# mcu.net
KiCad netlist of a schematic drawn in Altium Designer
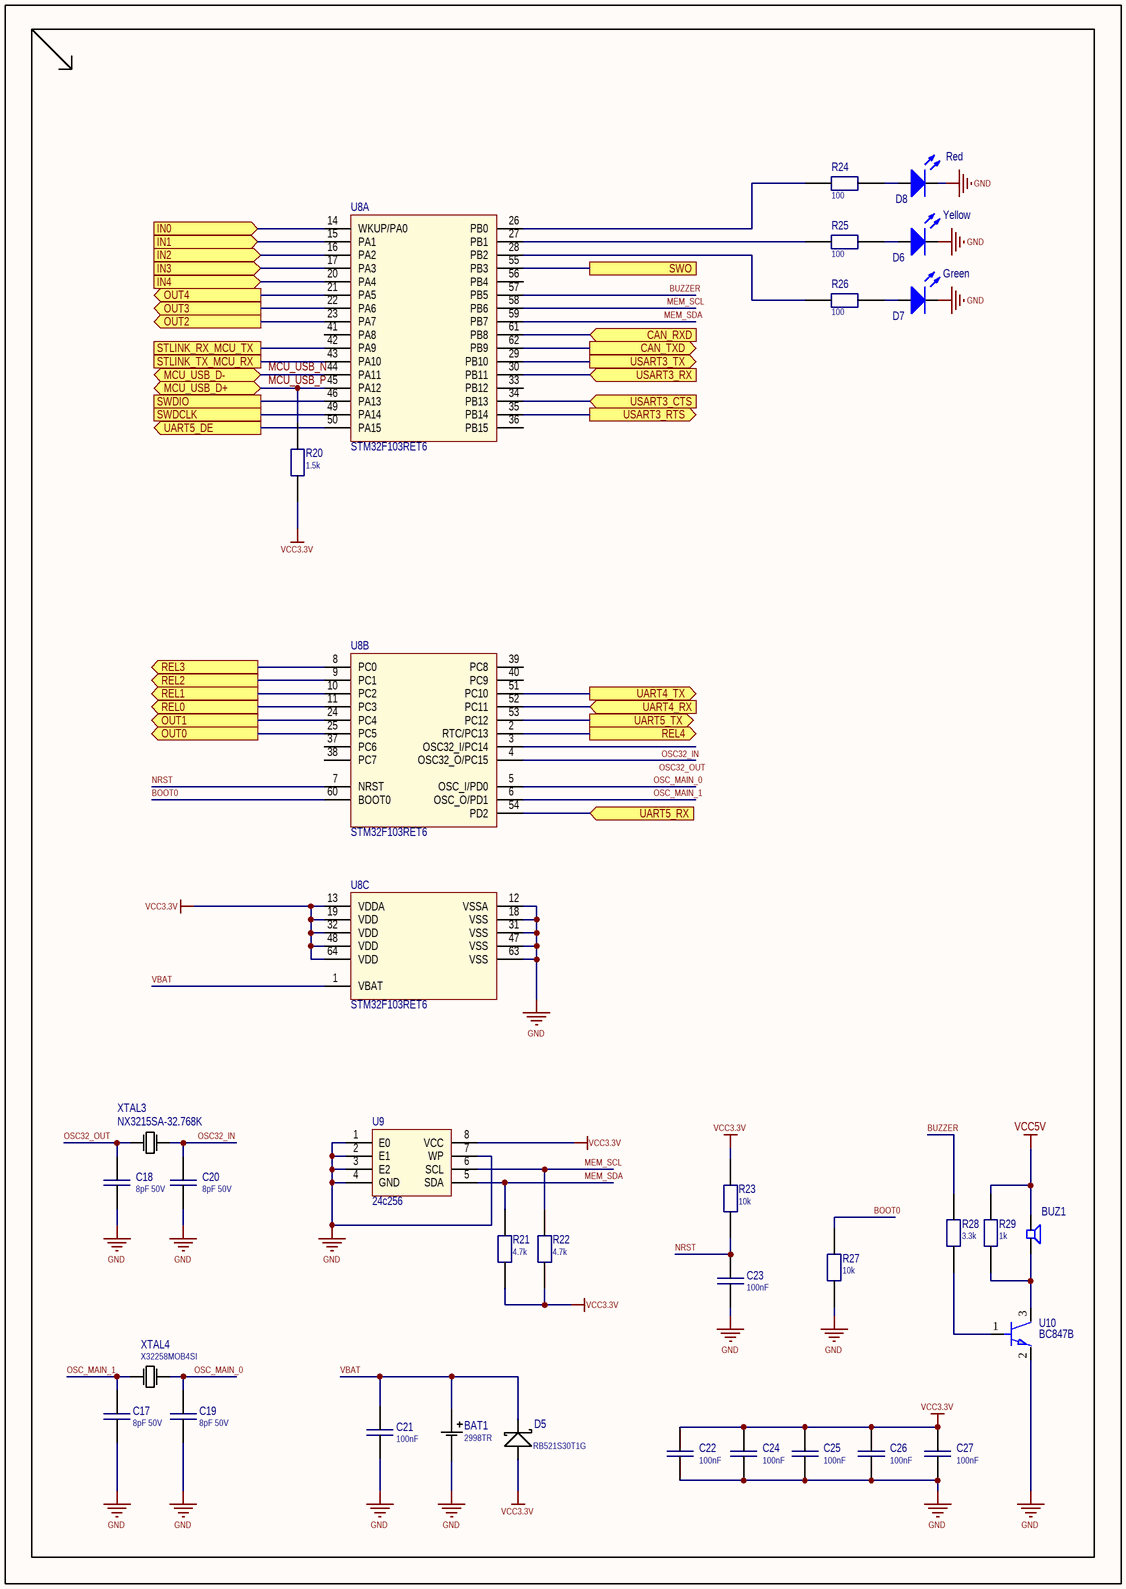
[diagram p0: mcu.schdoc]

(export (version "E")
  (design (tool "Eeschema 10.0.6"))
  (components
    (comp (ref "BAT1")
      (value "2998TR")
      (footprint "BAT_2998TR")
      (description "Battery")
      (libsource (lib "battery_socets") (part "2998TR"))
    )
    (comp (ref "BUZ1")
      (value "L-KLS3-SMT-09X1.8")
      (footprint "SPKR_PKMCS0909E4000-R1")
      (description "Piezoelectric Sounders")
      (fields (field (name "ALTERNATIVE PART") "PKMCS0909E4000-R1"))
      (libsource (lib "other") (part "BUZZER"))
    )
    (comp (ref "C17")
      (value "8pF 50V")
      (footprint "C_0603")
      (description "Capacitor")
      (fields (field (name "PART NUMBER") "CC0603DRNPO9BN8R0"))
      (libsource (lib "capacitors") (part "C0603"))
    )
    (comp (ref "C18")
      (value "8pF 50V")
      (footprint "C_0603")
      (description "Capacitor")
      (fields (field (name "PART NUMBER") "CC0603DRNPO9BN8R0"))
      (libsource (lib "capacitors") (part "C0603"))
    )
    (comp (ref "C19")
      (value "8pF 50V")
      (footprint "C_0603")
      (description "Capacitor")
      (fields (field (name "PART NUMBER") "CC0603DRNPO9BN8R0"))
      (libsource (lib "capacitors") (part "C0603"))
    )
    (comp (ref "C20")
      (value "8pF 50V")
      (footprint "C_0603")
      (description "Capacitor")
      (fields (field (name "PART NUMBER") "CC0603DRNPO9BN8R0"))
      (libsource (lib "capacitors") (part "C0603"))
    )
    (comp (ref "C21")
      (value "100nF")
      (footprint "C_0603")
      (description "Capacitor")
      (fields (field (name "PART NUMBER") "CC0603JPX7R9BB104"))
      (libsource (lib "capacitors") (part "C0603"))
    )
    (comp (ref "C22")
      (value "100nF")
      (footprint "C_0603")
      (description "Capacitor")
      (fields (field (name "PART NUMBER") "CC0603JPX7R9BB104"))
      (libsource (lib "capacitors") (part "C0603"))
    )
    (comp (ref "C23")
      (value "100nF")
      (footprint "C_0603")
      (description "Capacitor")
      (fields (field (name "PART NUMBER") "CC0603JPX7R9BB104"))
      (libsource (lib "capacitors") (part "C0603"))
    )
    (comp (ref "C24")
      (value "100nF")
      (footprint "C_0603")
      (description "Capacitor")
      (fields (field (name "PART NUMBER") "CC0603JPX7R9BB104"))
      (libsource (lib "capacitors") (part "C0603"))
    )
    (comp (ref "C25")
      (value "100nF")
      (footprint "C_0603")
      (description "Capacitor")
      (fields (field (name "PART NUMBER") "CC0603JPX7R9BB104"))
      (libsource (lib "capacitors") (part "C0603"))
    )
    (comp (ref "C26")
      (value "100nF")
      (footprint "C_0603")
      (description "Capacitor")
      (fields (field (name "PART NUMBER") "CC0603JPX7R9BB104"))
      (libsource (lib "capacitors") (part "C0603"))
    )
    (comp (ref "C27")
      (value "100nF")
      (footprint "C_0603")
      (description "Capacitor")
      (fields (field (name "PART NUMBER") "CC0603JPX7R9BB104"))
      (libsource (lib "capacitors") (part "C0603"))
    )
    (comp (ref "D5")
      (value "RB521S30T1G")
      (footprint "SOD-523")
      (description "Diode")
      (libsource (lib "diode") (part "D_SOD523"))
    )
    (comp (ref "D6")
      (value "Yellow")
      (footprint "LED_1206")
      (description "Typical INFRARED GaAs LED")
      (fields (field (name "PART NUMBER") "KPT-3216SYC"))
      (libsource (lib "AX_Altium_v2.3") (part "LED_SMT_1206"))
    )
    (comp (ref "D7")
      (value "Green")
      (footprint "LED_1206")
      (description "Typical INFRARED GaAs LED")
      (fields (field (name "PART NUMBER") "KP-3216SGD"))
      (libsource (lib "AX_Altium_v2.3") (part "LED_SMT_1206"))
    )
    (comp (ref "D8")
      (value "Red")
      (footprint "LED_1206")
      (description "Typical INFRARED GaAs LED")
      (fields (field (name "PART NUMBER") "KP-3216SRD"))
      (libsource (lib "AX_Altium_v2.3") (part "LED_SMT_1206"))
    )
    (comp (ref "R20")
      (value "1.5k")
      (footprint "R_0603")
      (description "Resistor")
      (fields (field (name "PART NUMBER") "RC0603FR-071K5L"))
      (libsource (lib "resistors") (part "RES_SMD"))
    )
    (comp (ref "R21")
      (value "4.7k")
      (footprint "R_0603")
      (description "Resistor")
      (fields (field (name "PART NUMBER") "RC0603FR-074K7L"))
      (libsource (lib "resistors") (part "RES_SMD"))
    )
    (comp (ref "R22")
      (value "4.7k")
      (footprint "R_0603")
      (description "Resistor")
      (fields (field (name "PART NUMBER") "RC0603FR-074K7L"))
      (libsource (lib "resistors") (part "RES_SMD"))
    )
    (comp (ref "R23")
      (value "10k")
      (footprint "R_0603")
      (description "Resistor")
      (fields (field (name "PART NUMBER") "RC0603FR-0710KL"))
      (libsource (lib "resistors") (part "RES_SMD"))
    )
    (comp (ref "R24")
      (value "100")
      (footprint "R_0603")
      (description "Resistor")
      (fields (field (name "PART NUMBER") "RC0603FR-07100RL"))
      (libsource (lib "resistors") (part "RES_SMD"))
    )
    (comp (ref "R25")
      (value "100")
      (footprint "R_0603")
      (description "Resistor")
      (fields (field (name "PART NUMBER") "RC0603FR-07100RL"))
      (libsource (lib "resistors") (part "RES_SMD"))
    )
    (comp (ref "R26")
      (value "100")
      (footprint "R_0603")
      (description "Resistor")
      (fields (field (name "PART NUMBER") "RC0603FR-07100RL"))
      (libsource (lib "resistors") (part "RES_SMD"))
    )
    (comp (ref "R27")
      (value "10k")
      (footprint "R_0603")
      (description "Resistor")
      (fields (field (name "PART NUMBER") "RC0603FR-0710KL"))
      (libsource (lib "resistors") (part "RES_SMD"))
    )
    (comp (ref "R28")
      (value "3.3k")
      (footprint "R_0603")
      (description "Resistor")
      (fields (field (name "PART NUMBER") "RC0603FR-073K3L"))
      (libsource (lib "resistors") (part "RES_SMD"))
    )
    (comp (ref "R29")
      (value "1k")
      (footprint "R_0603")
      (description "Resistor")
      (fields (field (name "PART NUMBER") "RC0603FR-071KL"))
      (libsource (lib "resistors") (part "RES_SMD"))
    )
    (comp (ref "U8")
      (value "STM32F103RET6")
      (footprint "LQFP64")
      (libsource (lib "mcu") (part "STM32F103Rxx"))
    )
    (comp (ref "U9")
      (value "24c256")
      (footprint "SO-8_M")
      (description "256-Kbit I2C-compatible Serial EEPROM")
      (fields (field (name "PART NUMBER") "AT24C256C"))
      (libsource (lib "discret_ic") (part "24c256"))
    )
    (comp (ref "U10")
      (value "BC847B")
      (footprint "SOT23")
      (description "45V 200mW 200@2mA,5V 100mA NPN SOT-23-3 Bipolar (BJT)")
      (libsource (lib "AX_Altium_v2.3") (part "BC847B"))
    )
    (comp (ref "XTAL3")
      (value "NX3215SA-32.768K")
      (footprint "XTAL_NX3215SA-32.768K-STD-MUA-8")
      (description "Crystal Oscillator")
      (fields (field (name "PART NUMBER") "NX3215SA-32.768K-10PPM-45KOHM-6PF"))
      (libsource (lib "crystals_oscillators") (part "NX3215SA-32.768K"))
    )
    (comp (ref "XTAL4")
      (value "X32258MOB4SI")
      (footprint "NX3225GA")
      (description "Crystal Oscillator")
      (libsource (lib "bmplc") (part "NX3225GA"))
    )
  )
  (nets
    (net (code "1") (name "/BOOT0") (class "Default")
      (node (ref "R27") (pin "2") (pinfunction "2_2") (pintype "passive"))
      (node (ref "U8") (pin "60") (pinfunction "BOOT0_60") (pintype "passive"))
    )
    (net (code "2") (name "/BUZZER") (class "Default")
      (node (ref "R28") (pin "1") (pinfunction "1_1") (pintype "passive"))
      (node (ref "U8") (pin "57") (pinfunction "PB5_57") (pintype "passive"))
    )
    (net (code "3") (name "/CAN_RXD") (class "Default")
      (node (ref "U8") (pin "61") (pinfunction "PB8_61") (pintype "passive"))
    )
    (net (code "4") (name "/CAN_TXD") (class "Default")
      (node (ref "U8") (pin "62") (pinfunction "PB9_62") (pintype "passive"))
    )
    (net (code "5") (name "/IN0") (class "Default")
      (node (ref "U8") (pin "14") (pinfunction "WKUP/PA0_14") (pintype "passive"))
    )
    (net (code "6") (name "/IN1") (class "Default")
      (node (ref "U8") (pin "15") (pinfunction "PA1_15") (pintype "passive"))
    )
    (net (code "7") (name "/IN2") (class "Default")
      (node (ref "U8") (pin "16") (pinfunction "PA2_16") (pintype "passive"))
    )
    (net (code "8") (name "/IN3") (class "Default")
      (node (ref "U8") (pin "17") (pinfunction "PA3_17") (pintype "passive"))
    )
    (net (code "9") (name "/IN4") (class "Default")
      (node (ref "U8") (pin "20") (pinfunction "PA4_20") (pintype "passive"))
    )
    (net (code "10") (name "/MCU_USB_N") (class "Default")
      (node (ref "U8") (pin "44") (pinfunction "PA11_44") (pintype "passive"))
    )
    (net (code "11") (name "/MCU_USB_P") (class "Default")
      (node (ref "R20") (pin "1") (pinfunction "1_1") (pintype "passive"))
      (node (ref "U8") (pin "45") (pinfunction "PA12_45") (pintype "passive"))
    )
    (net (code "12") (name "/MEM_SCL") (class "Default")
      (node (ref "R22") (pin "1") (pinfunction "1_1") (pintype "passive"))
      (node (ref "U8") (pin "58") (pinfunction "PB6_58") (pintype "passive"))
      (node (ref "U9") (pin "6") (pinfunction "SCL_6") (pintype "passive"))
    )
    (net (code "13") (name "/MEM_SDA") (class "Default")
      (node (ref "R21") (pin "1") (pinfunction "1_1") (pintype "passive"))
      (node (ref "U8") (pin "59") (pinfunction "PB7_59") (pintype "passive"))
      (node (ref "U9") (pin "5") (pinfunction "SDA_5") (pintype "passive"))
    )
    (net (code "14") (name "/NRST") (class "Default")
      (node (ref "C23") (pin "2") (pinfunction "2_2") (pintype "passive"))
      (node (ref "R23") (pin "1") (pinfunction "1_1") (pintype "passive"))
      (node (ref "U8") (pin "7") (pinfunction "NRST_7") (pintype "passive"))
    )
    (net (code "15") (name "/OSC32_IN") (class "Default")
      (node (ref "C20") (pin "2") (pinfunction "2_2") (pintype "passive"))
      (node (ref "U8") (pin "3") (pinfunction "OSC32_I/PC14_3") (pintype "passive"))
      (node (ref "XTAL3") (pin "2") (pinfunction "OSC2_2") (pintype "passive"))
    )
    (net (code "16") (name "/OSC32_OUT") (class "Default")
      (node (ref "C18") (pin "2") (pinfunction "2_2") (pintype "passive"))
      (node (ref "U8") (pin "4") (pinfunction "OSC32_O/PC15_4") (pintype "passive"))
      (node (ref "XTAL3") (pin "1") (pinfunction "OSC1_1") (pintype "passive"))
    )
    (net (code "17") (name "/OSC_MAIN_0") (class "Default")
      (node (ref "C19") (pin "2") (pinfunction "2_2") (pintype "passive"))
      (node (ref "U8") (pin "5") (pinfunction "OSC_I/PD0_5") (pintype "passive"))
      (node (ref "XTAL4") (pin "3") (pinfunction "OSC2_3") (pintype "passive"))
    )
    (net (code "18") (name "/OSC_MAIN_1") (class "Default")
      (node (ref "C17") (pin "2") (pinfunction "2_2") (pintype "passive"))
      (node (ref "U8") (pin "6") (pinfunction "OSC_O/PD1_6") (pintype "passive"))
      (node (ref "XTAL4") (pin "1") (pinfunction "OSC1_1") (pintype "passive"))
    )
    (net (code "19") (name "/OUT0") (class "Default")
      (node (ref "U8") (pin "25") (pinfunction "PC5_25") (pintype "passive"))
    )
    (net (code "20") (name "/OUT1") (class "Default")
      (node (ref "U8") (pin "24") (pinfunction "PC4_24") (pintype "passive"))
    )
    (net (code "21") (name "/OUT2") (class "Default")
      (node (ref "U8") (pin "23") (pinfunction "PA7_23") (pintype "passive"))
    )
    (net (code "22") (name "/OUT3") (class "Default")
      (node (ref "U8") (pin "22") (pinfunction "PA6_22") (pintype "passive"))
    )
    (net (code "23") (name "/OUT4") (class "Default")
      (node (ref "U8") (pin "21") (pinfunction "PA5_21") (pintype "passive"))
    )
    (net (code "24") (name "/REL0") (class "Default")
      (node (ref "U8") (pin "11") (pinfunction "PC3_11") (pintype "passive"))
    )
    (net (code "25") (name "/REL1") (class "Default")
      (node (ref "U8") (pin "10") (pinfunction "PC2_10") (pintype "passive"))
    )
    (net (code "26") (name "/REL2") (class "Default")
      (node (ref "U8") (pin "9") (pinfunction "PC1_9") (pintype "passive"))
    )
    (net (code "27") (name "/REL3") (class "Default")
      (node (ref "U8") (pin "8") (pinfunction "PC0_8") (pintype "passive"))
    )
    (net (code "28") (name "/REL4") (class "Default")
      (node (ref "U8") (pin "2") (pinfunction "RTC/PC13_2") (pintype "passive"))
    )
    (net (code "29") (name "/STLINK_RX_MCU_TX") (class "Default")
      (node (ref "U8") (pin "42") (pinfunction "PA9_42") (pintype "passive"))
    )
    (net (code "30") (name "/STLINK_TX_MCU_RX") (class "Default")
      (node (ref "U8") (pin "43") (pinfunction "PA10_43") (pintype "passive"))
    )
    (net (code "31") (name "/SWDCLK") (class "Default")
      (node (ref "U8") (pin "49") (pinfunction "PA14_49") (pintype "passive"))
    )
    (net (code "32") (name "/SWDIO") (class "Default")
      (node (ref "U8") (pin "46") (pinfunction "PA13_46") (pintype "passive"))
    )
    (net (code "33") (name "/SWO") (class "Default")
      (node (ref "U8") (pin "55") (pinfunction "PB3_55") (pintype "passive"))
    )
    (net (code "34") (name "/UART4_RX") (class "Default")
      (node (ref "U8") (pin "52") (pinfunction "PC11_52") (pintype "passive"))
    )
    (net (code "35") (name "/UART4_TX") (class "Default")
      (node (ref "U8") (pin "51") (pinfunction "PC10_51") (pintype "passive"))
    )
    (net (code "36") (name "/UART5_DE") (class "Default")
      (node (ref "U8") (pin "50") (pinfunction "PA15_50") (pintype "passive"))
    )
    (net (code "37") (name "/UART5_RX") (class "Default")
      (node (ref "U8") (pin "54") (pinfunction "PD2_54") (pintype "passive"))
    )
    (net (code "38") (name "/UART5_TX") (class "Default")
      (node (ref "U8") (pin "53") (pinfunction "PC12_53") (pintype "passive"))
    )
    (net (code "39") (name "/USART3_CTS") (class "Default")
      (node (ref "U8") (pin "34") (pinfunction "PB13_34") (pintype "passive"))
    )
    (net (code "40") (name "/USART3_RTS") (class "Default")
      (node (ref "U8") (pin "35") (pinfunction "PB14_35") (pintype "passive"))
    )
    (net (code "41") (name "/USART3_RX") (class "Default")
      (node (ref "U8") (pin "30") (pinfunction "PB11_30") (pintype "passive"))
    )
    (net (code "42") (name "/USART3_TX") (class "Default")
      (node (ref "U8") (pin "29") (pinfunction "PB10_29") (pintype "passive"))
    )
    (net (code "43") (name "/VBAT") (class "Default")
      (node (ref "BAT1") (pin "P1") (pinfunction "+_P1") (pintype "passive"))
      (node (ref "C21") (pin "2") (pinfunction "2_2") (pintype "passive"))
      (node (ref "D5") (pin "1") (pinfunction "K_1") (pintype "passive"))
      (node (ref "U8") (pin "1") (pinfunction "VBAT_1") (pintype "power_in"))
    )
    (net (code "44") (name "GND") (class "Default")
      (node (ref "BAT1") (pin "N") (pinfunction "-_N") (pintype "passive"))
      (node (ref "C17") (pin "1") (pinfunction "1_1") (pintype "passive"))
      (node (ref "C18") (pin "1") (pinfunction "1_1") (pintype "passive"))
      (node (ref "C19") (pin "1") (pinfunction "1_1") (pintype "passive"))
      (node (ref "C20") (pin "1") (pinfunction "1_1") (pintype "passive"))
      (node (ref "C21") (pin "1") (pinfunction "1_1") (pintype "passive"))
      (node (ref "C22") (pin "1") (pinfunction "1_1") (pintype "passive"))
      (node (ref "C23") (pin "1") (pinfunction "1_1") (pintype "passive"))
      (node (ref "C24") (pin "1") (pinfunction "1_1") (pintype "passive"))
      (node (ref "C25") (pin "1") (pinfunction "1_1") (pintype "passive"))
      (node (ref "C26") (pin "1") (pinfunction "1_1") (pintype "passive"))
      (node (ref "C27") (pin "1") (pinfunction "1_1") (pintype "passive"))
      (node (ref "D6") (pin "2") (pinfunction "K_2") (pintype "passive"))
      (node (ref "D7") (pin "2") (pinfunction "K_2") (pintype "passive"))
      (node (ref "D8") (pin "2") (pinfunction "K_2") (pintype "passive"))
      (node (ref "R27") (pin "1") (pinfunction "1_1") (pintype "passive"))
      (node (ref "U10") (pin "2") (pintype "passive"))
      (node (ref "U8") (pin "12") (pinfunction "VSSA_12") (pintype "power_in"))
      (node (ref "U8") (pin "18") (pinfunction "VSS_18") (pintype "power_in"))
      (node (ref "U8") (pin "31") (pinfunction "VSS_31") (pintype "power_in"))
      (node (ref "U8") (pin "47") (pinfunction "VSS_47") (pintype "power_in"))
      (node (ref "U8") (pin "63") (pinfunction "VSS_63") (pintype "power_in"))
      (node (ref "U9") (pin "1") (pinfunction "E0_1") (pintype "passive"))
      (node (ref "U9") (pin "2") (pinfunction "E1_2") (pintype "passive"))
      (node (ref "U9") (pin "3") (pinfunction "E2_3") (pintype "passive"))
      (node (ref "U9") (pin "4") (pinfunction "GND_4") (pintype "passive"))
      (node (ref "U9") (pin "7") (pinfunction "WP_7") (pintype "passive"))
    )
    (net (code "45") (name "Net-(BUZ1-Pad2)") (class "Default")
      (node (ref "BUZ1") (pin "2") (pinfunction "2_2") (pintype "passive"))
      (node (ref "R29") (pin "1") (pinfunction "1_1") (pintype "passive"))
      (node (ref "U10") (pin "3") (pintype "passive"))
    )
    (net (code "46") (name "Net-(D6-A)") (class "Default")
      (node (ref "D6") (pin "1") (pinfunction "A_1") (pintype "passive"))
      (node (ref "R25") (pin "1") (pinfunction "1_1") (pintype "passive"))
    )
    (net (code "47") (name "Net-(D7-A)") (class "Default")
      (node (ref "D7") (pin "1") (pinfunction "A_1") (pintype "passive"))
      (node (ref "R26") (pin "1") (pinfunction "1_1") (pintype "passive"))
    )
    (net (code "48") (name "Net-(D8-A)") (class "Default")
      (node (ref "D8") (pin "1") (pinfunction "A_1") (pintype "passive"))
      (node (ref "R24") (pin "1") (pinfunction "1_1") (pintype "passive"))
    )
    (net (code "49") (name "Net-(R28-Pad2)") (class "Default")
      (node (ref "R28") (pin "2") (pinfunction "2_2") (pintype "passive"))
      (node (ref "U10") (pin "1") (pintype "passive"))
    )
    (net (code "50") (name "Net-(U8A-PB0)") (class "Default")
      (node (ref "R24") (pin "2") (pinfunction "2_2") (pintype "passive"))
      (node (ref "U8") (pin "26") (pinfunction "PB0_26") (pintype "passive"))
    )
    (net (code "51") (name "Net-(U8A-PB1)") (class "Default")
      (node (ref "R25") (pin "2") (pinfunction "2_2") (pintype "passive"))
      (node (ref "U8") (pin "27") (pinfunction "PB1_27") (pintype "passive"))
    )
    (net (code "52") (name "Net-(U8A-PB2)") (class "Default")
      (node (ref "R26") (pin "2") (pinfunction "2_2") (pintype "passive"))
      (node (ref "U8") (pin "28") (pinfunction "PB2_28") (pintype "passive"))
    )
    (net (code "53") (name "VCC3.3V") (class "Default")
      (node (ref "C22") (pin "2") (pinfunction "2_2") (pintype "passive"))
      (node (ref "C24") (pin "2") (pinfunction "2_2") (pintype "passive"))
      (node (ref "C25") (pin "2") (pinfunction "2_2") (pintype "passive"))
      (node (ref "C26") (pin "2") (pinfunction "2_2") (pintype "passive"))
      (node (ref "C27") (pin "2") (pinfunction "2_2") (pintype "passive"))
      (node (ref "D5") (pin "2") (pinfunction "A_2") (pintype "passive"))
      (node (ref "R20") (pin "2") (pinfunction "2_2") (pintype "passive"))
      (node (ref "R21") (pin "2") (pinfunction "2_2") (pintype "passive"))
      (node (ref "R22") (pin "2") (pinfunction "2_2") (pintype "passive"))
      (node (ref "R23") (pin "2") (pinfunction "2_2") (pintype "passive"))
      (node (ref "U8") (pin "13") (pinfunction "VDDA_13") (pintype "power_in"))
      (node (ref "U8") (pin "19") (pinfunction "VDD_19") (pintype "power_in"))
      (node (ref "U8") (pin "32") (pinfunction "VDD_32") (pintype "power_in"))
      (node (ref "U8") (pin "48") (pinfunction "VDD_48") (pintype "power_in"))
      (node (ref "U8") (pin "64") (pinfunction "VDD_64") (pintype "power_in"))
      (node (ref "U9") (pin "8") (pinfunction "VCC_8") (pintype "passive"))
    )
    (net (code "54") (name "VCC5V") (class "Default")
      (node (ref "BUZ1") (pin "1") (pinfunction "1_1") (pintype "passive"))
      (node (ref "R29") (pin "2") (pinfunction "2_2") (pintype "passive"))
    )
    (net (code "55") (name "unconnected-(U8A-PA8-Pad41)") (class "Default")
      (node (ref "U8") (pin "41") (pinfunction "PA8_41") (pintype "passive"))
    )
    (net (code "56") (name "unconnected-(U8A-PB4-Pad56)") (class "Default")
      (node (ref "U8") (pin "56") (pinfunction "PB4_56") (pintype "passive"))
    )
    (net (code "57") (name "unconnected-(U8A-PB12-Pad33)") (class "Default")
      (node (ref "U8") (pin "33") (pinfunction "PB12_33") (pintype "passive"))
    )
    (net (code "58") (name "unconnected-(U8A-PB15-Pad36)") (class "Default")
      (node (ref "U8") (pin "36") (pinfunction "PB15_36") (pintype "passive"))
    )
    (net (code "59") (name "unconnected-(U8B-PC6-Pad37)") (class "Default")
      (node (ref "U8") (pin "37") (pinfunction "PC6_37") (pintype "passive"))
    )
    (net (code "60") (name "unconnected-(U8B-PC7-Pad38)") (class "Default")
      (node (ref "U8") (pin "38") (pinfunction "PC7_38") (pintype "passive"))
    )
    (net (code "61") (name "unconnected-(U8B-PC8-Pad39)") (class "Default")
      (node (ref "U8") (pin "39") (pinfunction "PC8_39") (pintype "passive"))
    )
    (net (code "62") (name "unconnected-(U8B-PC9-Pad40)") (class "Default")
      (node (ref "U8") (pin "40") (pinfunction "PC9_40") (pintype "passive"))
    )
  )
)
